# MB1184.net
KiCad netlist of a schematic drawn in Altium Designer
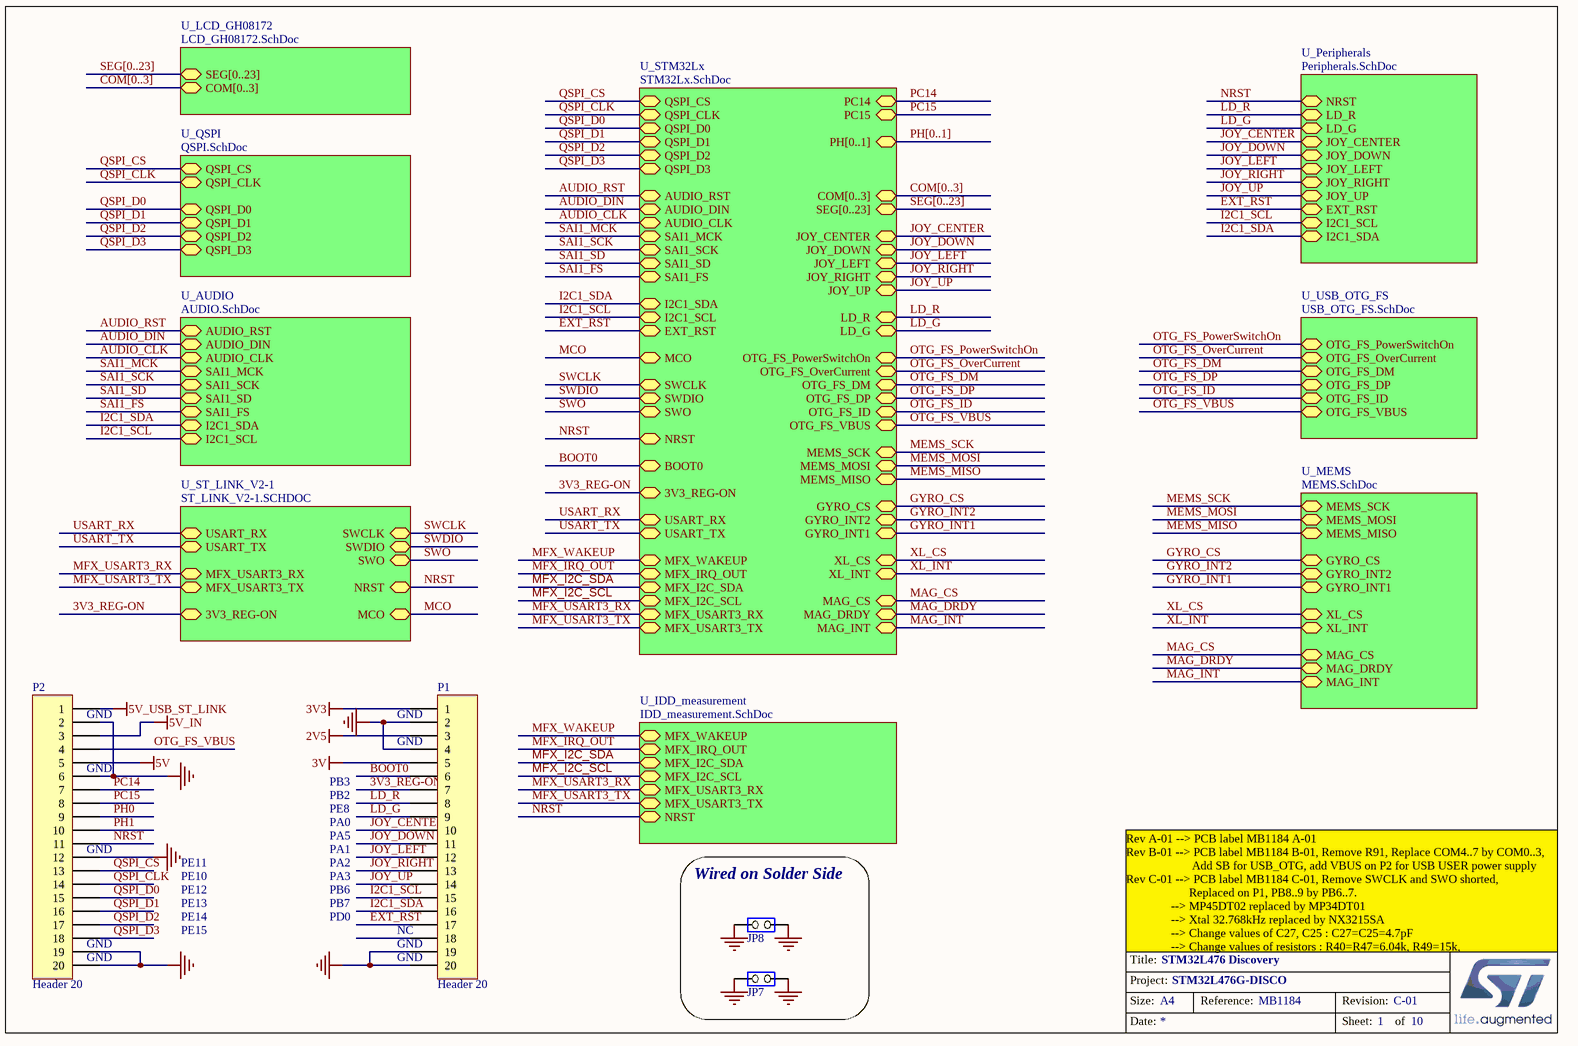
[diagram p0: MB1184.SchDoc]

(export (version "E")
  (design (tool "Eeschema 10.0.6"))
  (components
    (comp (ref "JP7")
      (value "Jumper 2 pins")
      (footprint "SIP2/2.54")
      (libsource (lib "MCD_TOOLS") (part "Jumper2"))
    )
    (comp (ref "JP8")
      (value "Jumper 2 pins")
      (footprint "SIP2/2.54")
      (libsource (lib "MCD_TOOLS") (part "Jumper2"))
    )
    (comp (ref "P1")
      (value "Header 20")
      (footprint "HDR1X20")
      (description "Header, 20-Pin")
      (fields (field (name "PUBLISHER") "Altium Limited"))
      (libsource (lib "") (part "Header 20_1"))
    )
    (comp (ref "P2")
      (value "Header 20")
      (footprint "HDR1X20")
      (description "Header, 20-Pin")
      (fields (field (name "PUBLISHER") "Altium Limited"))
      (libsource (lib "Miscellaneous Connectors") (part "Header 20"))
    )
  )
  (nets
    (net (code "29") (name "/3V3_REG-ON") (class "Default")
      (node (ref "P1") (pin "7") (pinfunction "7_7") (pintype "passive"))
    )
    (net (code "33") (name "/BOOT0") (class "Default")
      (node (ref "P1") (pin "6") (pinfunction "6_6") (pintype "passive"))
    )
    (net (code "35") (name "/EXT_RST") (class "Default")
      (node (ref "P1") (pin "17") (pinfunction "17_17") (pintype "passive"))
    )
    (net (code "39") (name "/I2C1_SCL") (class "Default")
      (node (ref "P1") (pin "15") (pinfunction "15_15") (pintype "passive"))
    )
    (net (code "40") (name "/I2C1_SDA") (class "Default")
      (node (ref "P1") (pin "16") (pinfunction "16_16") (pintype "passive"))
    )
    (net (code "41") (name "/JOY_CENTER") (class "Default")
      (node (ref "P1") (pin "10") (pinfunction "10_10") (pintype "passive"))
    )
    (net (code "42") (name "/JOY_DOWN") (class "Default")
      (node (ref "P1") (pin "11") (pinfunction "11_11") (pintype "passive"))
    )
    (net (code "43") (name "/JOY_LEFT") (class "Default")
      (node (ref "P1") (pin "12") (pinfunction "12_12") (pintype "passive"))
    )
    (net (code "44") (name "/JOY_RIGHT") (class "Default")
      (node (ref "P1") (pin "13") (pinfunction "13_13") (pintype "passive"))
    )
    (net (code "45") (name "/JOY_UP") (class "Default")
      (node (ref "P1") (pin "14") (pinfunction "14_14") (pintype "passive"))
    )
    (net (code "46") (name "/LD_G") (class "Default")
      (node (ref "P1") (pin "9") (pinfunction "9_9") (pintype "passive"))
    )
    (net (code "47") (name "/LD_R") (class "Default")
      (node (ref "P1") (pin "8") (pinfunction "8_8") (pintype "passive"))
    )
    (net (code "61") (name "/NRST") (class "Default")
      (node (ref "P2") (pin "11") (pinfunction "11_11") (pintype "passive"))
    )
    (net (code "67") (name "/OTG_FS_VBUS") (class "Default")
      (node (ref "P2") (pin "4") (pinfunction "4_4") (pintype "passive"))
    )
    (net (code "68") (name "/PC14") (class "Default")
      (node (ref "P2") (pin "7") (pinfunction "7_7") (pintype "passive"))
    )
    (net (code "69") (name "/PC15") (class "Default")
      (node (ref "P2") (pin "8") (pinfunction "8_8") (pintype "passive"))
    )
    (net (code "70") (name "/PH0") (class "Default")
      (node (ref "P2") (pin "9") (pinfunction "9_9") (pintype "passive"))
    )
    (net (code "71") (name "/PH1") (class "Default")
      (node (ref "P2") (pin "10") (pinfunction "10_10") (pintype "passive"))
    )
    (net (code "73") (name "/QSPI_CLK") (class "Default")
      (node (ref "P2") (pin "14") (pinfunction "14_14") (pintype "passive"))
    )
    (net (code "74") (name "/QSPI_CS") (class "Default")
      (node (ref "P2") (pin "13") (pinfunction "13_13") (pintype "passive"))
    )
    (net (code "75") (name "/QSPI_D0") (class "Default")
      (node (ref "P2") (pin "15") (pinfunction "15_15") (pintype "passive"))
    )
    (net (code "76") (name "/QSPI_D1") (class "Default")
      (node (ref "P2") (pin "16") (pinfunction "16_16") (pintype "passive"))
    )
    (net (code "77") (name "/QSPI_D2") (class "Default")
      (node (ref "P2") (pin "17") (pinfunction "17_17") (pintype "passive"))
    )
    (net (code "78") (name "/QSPI_D3") (class "Default")
      (node (ref "P2") (pin "18") (pinfunction "18_18") (pintype "passive"))
    )
    (net (code "91") (name "2V5") (class "Default")
      (node (ref "P1") (pin "3") (pinfunction "3_3") (pintype "passive"))
    )
    (net (code "92") (name "3V") (class "Default")
      (node (ref "P1") (pin "5") (pinfunction "5_5") (pintype "passive"))
    )
    (net (code "93") (name "3V3") (class "Default")
      (node (ref "P1") (pin "1") (pinfunction "1_1") (pintype "passive"))
    )
    (net (code "94") (name "5V") (class "Default")
      (node (ref "P2") (pin "5") (pinfunction "5_5") (pintype "passive"))
    )
    (net (code "95") (name "5V_IN") (class "Default")
      (node (ref "P2") (pin "3") (pinfunction "3_3") (pintype "passive"))
    )
    (net (code "96") (name "5V_USB_ST_LINK") (class "Default")
      (node (ref "P2") (pin "1") (pinfunction "1_1") (pintype "passive"))
    )
    (net (code "97") (name "GND") (class "Default")
      (node (ref "JP7") (pin "1") (pinfunction "COMMON_1") (pintype "passive"))
      (node (ref "JP7") (pin "2") (pinfunction "NO_2") (pintype "passive"))
      (node (ref "JP8") (pin "1") (pinfunction "COMMON_1") (pintype "passive"))
      (node (ref "JP8") (pin "2") (pinfunction "NO_2") (pintype "passive"))
      (node (ref "P1") (pin "19") (pinfunction "19_19") (pintype "passive"))
      (node (ref "P1") (pin "2") (pinfunction "2_2") (pintype "passive"))
      (node (ref "P1") (pin "20") (pinfunction "20_20") (pintype "passive"))
      (node (ref "P1") (pin "4") (pinfunction "4_4") (pintype "passive"))
      (node (ref "P2") (pin "12") (pinfunction "12_12") (pintype "passive"))
      (node (ref "P2") (pin "19") (pinfunction "19_19") (pintype "passive"))
      (node (ref "P2") (pin "2") (pinfunction "2_2") (pintype "passive"))
      (node (ref "P2") (pin "20") (pinfunction "20_20") (pintype "passive"))
      (node (ref "P2") (pin "6") (pinfunction "6_6") (pintype "passive"))
    )
    (net (code "98") (name "unconnected-(P1-Pad18)") (class "Default")
      (node (ref "P1") (pin "18") (pinfunction "18_18") (pintype "passive"))
    )
  )
)
